# BlinkyBoard3.net
KiCad netlist of a schematic drawn in EAGLE
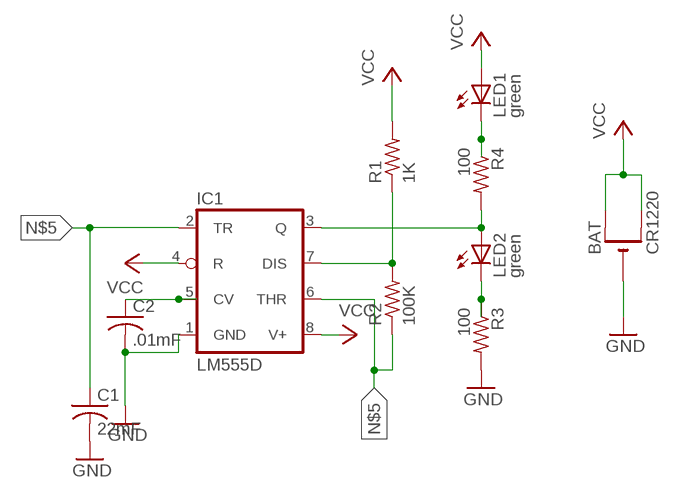
[diagram p0: schematic, sheet 1]

(export (version "E")
  (design (tool "Eeschema 10.0.6"))
  (components
    (comp (ref "BAT")
      (value "CR1220")
      (footprint "eagle-import:CR1220-SMD")
      (libsource (lib "eagle-import") (part "CR1220SMT"))
    )
    (comp (ref "C1")
      (value "22mF")
      (footprint "eagle-import:C0805")
      (libsource (lib "eagle-import") (part "C-USC0805"))
    )
    (comp (ref "C2")
      (value ".01mF")
      (footprint "eagle-import:C0805")
      (libsource (lib "eagle-import") (part "C-USC0805"))
    )
    (comp (ref "IC1")
      (value "LM555D")
      (footprint "eagle-import:SO08")
      (libsource (lib "eagle-import") (part "555DLM"))
    )
    (comp (ref "LED1")
      (value "green")
      (footprint "eagle-import:CHIPLED_0805")
      (libsource (lib "eagle-import") (part "LEDCHIPLED_0805"))
    )
    (comp (ref "LED2")
      (value "green")
      (footprint "eagle-import:CHIPLED_0805")
      (libsource (lib "eagle-import") (part "LEDCHIPLED_0805"))
    )
    (comp (ref "R1")
      (value "1K")
      (footprint "eagle-import:R0805")
      (libsource (lib "eagle-import") (part "R-US_R0805"))
    )
    (comp (ref "R2")
      (value "100K")
      (footprint "eagle-import:R0805")
      (libsource (lib "eagle-import") (part "R-US_R0805"))
    )
    (comp (ref "R3")
      (value "100")
      (footprint "eagle-import:R0805")
      (libsource (lib "eagle-import") (part "R-US_R0805"))
    )
    (comp (ref "R4")
      (value "100")
      (footprint "eagle-import:R0805")
      (libsource (lib "eagle-import") (part "R-US_R0805"))
    )
  )
  (nets
    (net (code "1") (name "GND") (class "Default")
      (node (ref "BAT") (pin "-") (pinfunction "-_-") (pintype "passive"))
      (node (ref "C1") (pin "2") (pinfunction "2_2") (pintype "passive"))
      (node (ref "C2") (pin "2") (pinfunction "2_2") (pintype "passive"))
      (node (ref "IC1") (pin "1") (pinfunction "GND_1") (pintype "power_in"))
      (node (ref "R3") (pin "2") (pinfunction "2_2") (pintype "passive"))
    )
    (net (code "2") (name "N$5") (class "Default")
      (node (ref "C1") (pin "1") (pinfunction "1_1") (pintype "passive"))
      (node (ref "IC1") (pin "2") (pinfunction "TR_2") (pintype "input"))
      (node (ref "IC1") (pin "6") (pinfunction "THR_6") (pintype "input"))
      (node (ref "R2") (pin "1") (pinfunction "1_1") (pintype "passive"))
    )
    (net (code "3") (name "Net-(IC1-CV)") (class "Default")
      (node (ref "C2") (pin "1") (pinfunction "1_1") (pintype "passive"))
      (node (ref "IC1") (pin "5") (pinfunction "CV_5") (pintype "input"))
    )
    (net (code "4") (name "Net-(IC1-DIS)") (class "Default")
      (node (ref "IC1") (pin "7") (pinfunction "DIS_7") (pintype "input"))
      (node (ref "R1") (pin "1") (pinfunction "1_1") (pintype "passive"))
      (node (ref "R2") (pin "2") (pinfunction "2_2") (pintype "passive"))
    )
    (net (code "5") (name "Net-(IC1-Q)") (class "Default")
      (node (ref "IC1") (pin "3") (pinfunction "Q_3") (pintype "output"))
      (node (ref "LED2") (pin "A") (pinfunction "A_A") (pintype "passive"))
      (node (ref "R4") (pin "2") (pinfunction "2_2") (pintype "passive"))
    )
    (net (code "6") (name "Net-(LED1-PadC)") (class "Default")
      (node (ref "LED1") (pin "C") (pinfunction "C_C") (pintype "passive"))
      (node (ref "R4") (pin "1") (pinfunction "1_1") (pintype "passive"))
    )
    (net (code "7") (name "Net-(LED2-PadC)") (class "Default")
      (node (ref "LED2") (pin "C") (pinfunction "C_C") (pintype "passive"))
      (node (ref "R3") (pin "1") (pinfunction "1_1") (pintype "passive"))
    )
    (net (code "8") (name "VCC") (class "Default")
      (node (ref "BAT") (pin "+$1") (pinfunction "+_+$1") (pintype "passive"))
      (node (ref "BAT") (pin "+$2") (pinfunction "+1_+$2") (pintype "passive"))
      (node (ref "IC1") (pin "4") (pinfunction "R_4") (pintype "input"))
      (node (ref "IC1") (pin "8") (pinfunction "V+_8") (pintype "power_in"))
      (node (ref "LED1") (pin "A") (pinfunction "A_A") (pintype "passive"))
      (node (ref "R1") (pin "2") (pinfunction "2_2") (pintype "passive"))
    )
  )
)
